# 468323_001_Audio.net
KiCad netlist of a schematic drawn in Altium Designer
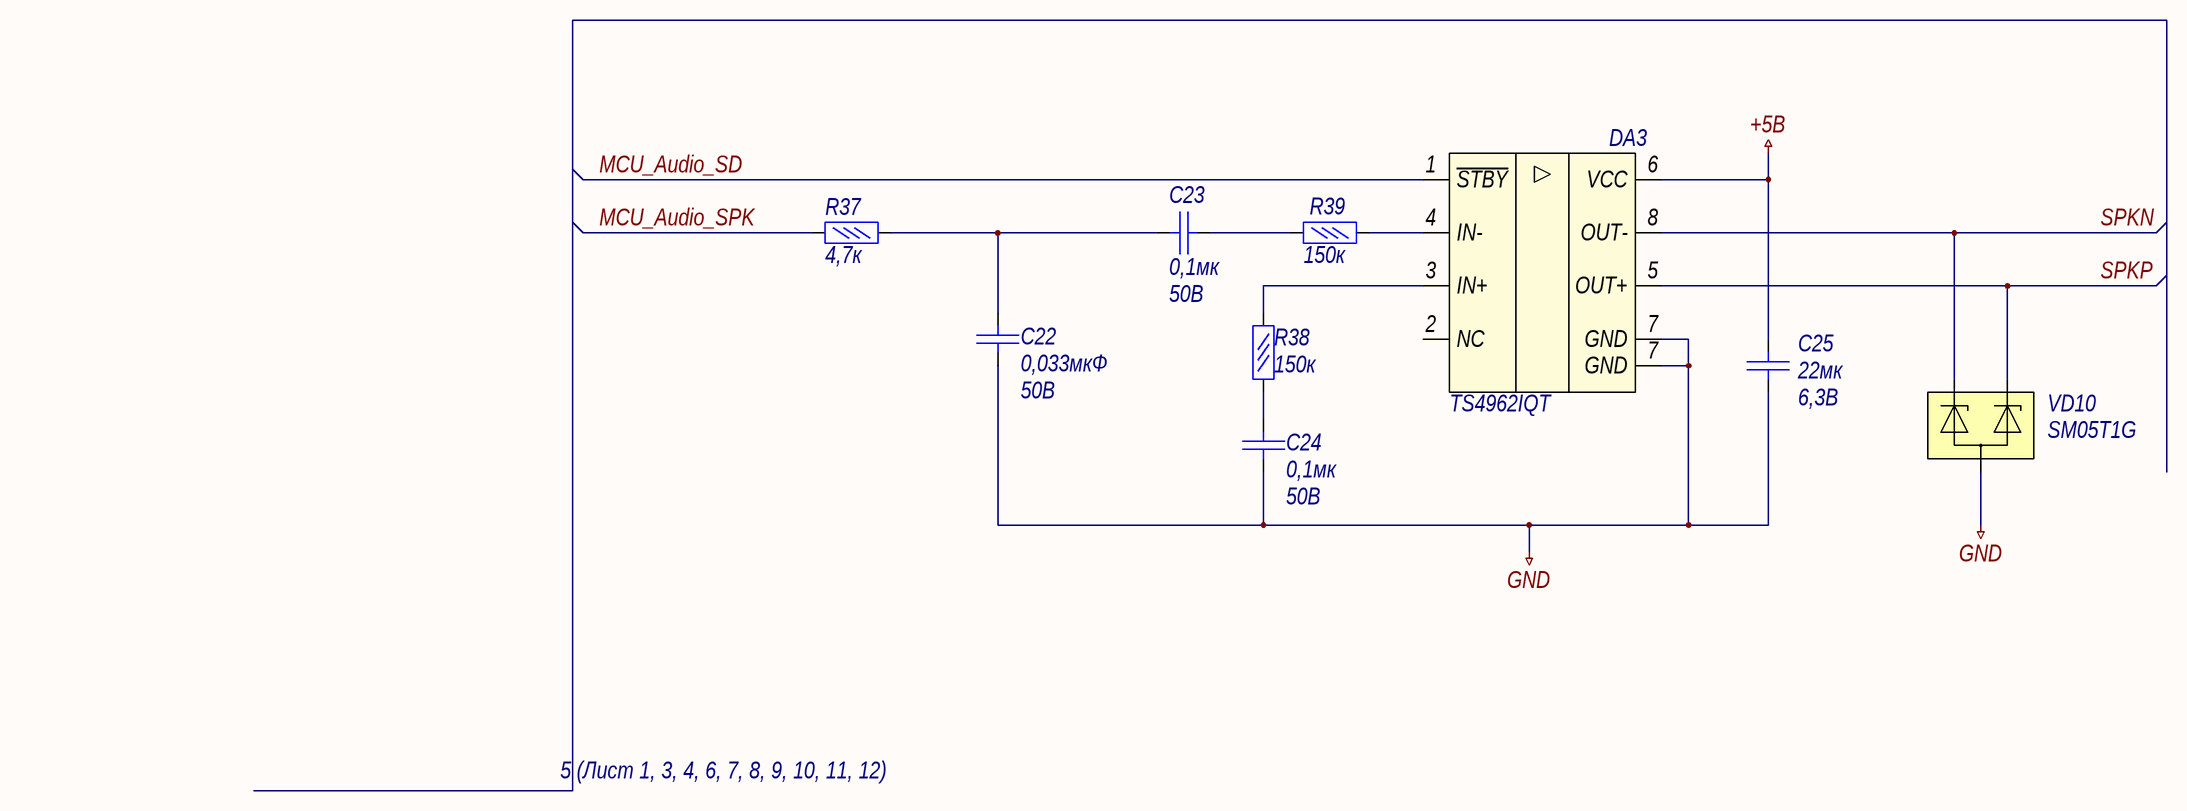
[diagram p0: РЕУН.468323.001_Audio.SchDoc]

(export (version "E")
  (design (tool "Eeschema 10.0.6"))
  (components
    (comp (ref "C22")
      (value "0,033мкФ")
      (footprint "C0805_AA")
      (description "Конденсатор кер.")
      (fields (field (name "VOLTAGE") "50В"))
      (libsource (lib "Library_Diana") (part "Конденсатор кер."))
    )
    (comp (ref "C23")
      (value "0,1мк")
      (footprint "C0805_AA")
      (description "Конденсатор кер.")
      (fields (field (name "VOLTAGE") "50В"))
      (libsource (lib "Library_Diana") (part "Конденсатор кер."))
    )
    (comp (ref "C24")
      (value "0,1мк")
      (footprint "C0805_AA")
      (description "Конденсатор кер.")
      (fields (field (name "VOLTAGE") "50В"))
      (libsource (lib "Library_Diana") (part "Конденсатор кер."))
    )
    (comp (ref "C25")
      (value "22мк")
      (footprint "C0805_AA")
      (description "Конденсатор кер.")
      (fields (field (name "VOLTAGE") "6,3В"))
      (libsource (lib "Library_Diana") (part "Конденсатор кер."))
    )
    (comp (ref "DA3")
      (value "TS4962IQT")
      (description "Audio Power Amplifier")
      (libsource (lib "Library_Diana") (part "TS4962"))
    )
    (comp (ref "R37")
      (value "4,7к")
      (footprint "R1206")
      (description "Резистор 0,05Вт")
      (libsource (lib "Library_Diana") (part "Резистор  0,05Вт"))
    )
    (comp (ref "R38")
      (value "150к")
      (footprint "R1206")
      (description "Резистор 0,05Вт")
      (libsource (lib "") (part "Резистор  0,05Вт_1"))
    )
    (comp (ref "R39")
      (value "150к")
      (footprint "R1206")
      (description "Резистор 0,05Вт")
      (libsource (lib "Library_Diana") (part "Резистор  0,05Вт"))
    )
    (comp (ref "VD10")
      (value "SM05T1G")
      (description "Сборка TVS-диодов")
      (libsource (lib "Library_Diana") (part "ZenerArray2"))
    )
  )
  (nets
    (net (code "1") (name "+5В") (class "Default")
      (node (ref "C25") (pin "2") (pinfunction "2_2") (pintype "passive"))
      (node (ref "DA3") (pin "6") (pinfunction "VCC_6") (pintype "passive"))
    )
    (net (code "2") (name "/MCU_Audio_SD") (class "Default")
      (node (ref "DA3") (pin "1") (pinfunction "~{STBY}_1") (pintype "passive"))
    )
    (net (code "3") (name "/MCU_Audio_SPK") (class "Default")
      (node (ref "R37") (pin "2") (pinfunction "2_2") (pintype "passive"))
    )
    (net (code "4") (name "/SPKN") (class "Default")
      (node (ref "DA3") (pin "8") (pinfunction "OUT-_8") (pintype "passive"))
      (node (ref "VD10") (pin "1") (pintype "passive"))
    )
    (net (code "5") (name "/SPKP") (class "Default")
      (node (ref "DA3") (pin "5") (pinfunction "OUT+_5") (pintype "passive"))
      (node (ref "VD10") (pin "2") (pintype "passive"))
    )
    (net (code "6") (name "GND") (class "Default")
      (node (ref "C22") (pin "1") (pinfunction "1_1") (pintype "passive"))
      (node (ref "C24") (pin "1") (pinfunction "1_1") (pintype "passive"))
      (node (ref "C25") (pin "1") (pinfunction "1_1") (pintype "passive"))
      (node (ref "DA3") (pin "7") (pinfunction "GND_7") (pintype "passive"))
      (node (ref "VD10") (pin "3") (pintype "passive"))
    )
    (net (code "7") (name "Net-(C22-Pad2)") (class "Default")
      (node (ref "C22") (pin "2") (pinfunction "2_2") (pintype "passive"))
      (node (ref "C23") (pin "2") (pinfunction "2_2") (pintype "passive"))
      (node (ref "R37") (pin "1") (pinfunction "1_1") (pintype "passive"))
    )
    (net (code "8") (name "Net-(C23-Pad1)") (class "Default")
      (node (ref "C23") (pin "1") (pinfunction "1_1") (pintype "passive"))
      (node (ref "R39") (pin "2") (pinfunction "2_2") (pintype "passive"))
    )
    (net (code "9") (name "Net-(C24-Pad2)") (class "Default")
      (node (ref "C24") (pin "2") (pinfunction "2_2") (pintype "passive"))
      (node (ref "R38") (pin "1") (pinfunction "1_1") (pintype "passive"))
    )
    (net (code "10") (name "Net-(DA3-IN+)") (class "Default")
      (node (ref "DA3") (pin "3") (pinfunction "IN+_3") (pintype "passive"))
      (node (ref "R38") (pin "2") (pinfunction "2_2") (pintype "passive"))
    )
    (net (code "11") (name "Net-(DA3-IN-)") (class "Default")
      (node (ref "DA3") (pin "4") (pinfunction "IN-_4") (pintype "passive"))
      (node (ref "R39") (pin "1") (pinfunction "1_1") (pintype "passive"))
    )
    (net (code "12") (name "unconnected-(DA3-NC-Pad2)") (class "Default")
      (node (ref "DA3") (pin "2") (pinfunction "NC_2") (pintype "passive"))
    )
  )
)
